# ext_supply_con.net
KiCad netlist of a schematic drawn in Altium Designer
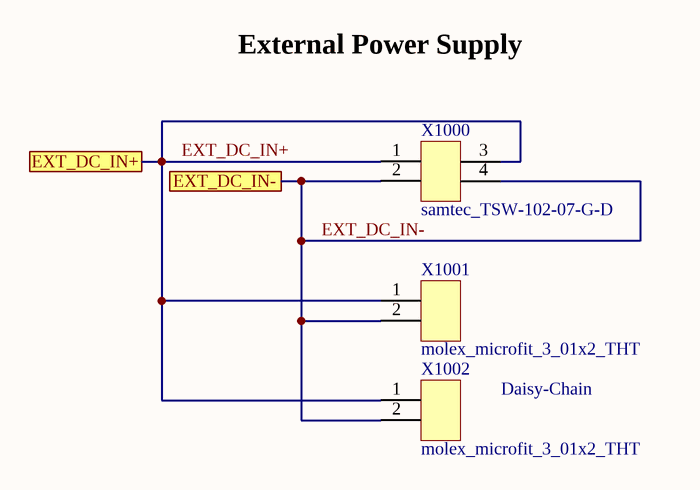
[diagram p0: ext_supply_con.SchDoc]

(export (version "E")
  (design (tool "Eeschema 10.0.6"))
  (components
    (comp (ref "X1000")
      (value "samtec_TSW-102-07-G-D")
      (footprint "Pinheader_2.54_2x2")
      (description "Board-To-Board Connector, Vertical, 2.54 mm, 4 Contacts, Header, TSW Series, Through Hole, 2 Rows")
      (fields (field (name "MANUFACTURER") "Samtec"))
      (libsource (lib "OE750") (part "X2x2"))
    )
    (comp (ref "X1001")
      (value "molex_microfit_3_01x2_THT")
      (footprint "MOLEX_MICROFIT_01x2_THT")
      (fields (field (name "MANUFACTURER") "Molex"))
      (libsource (lib "OE750") (part "X2"))
    )
    (comp (ref "X1002")
      (value "molex_microfit_3_01x2_THT")
      (footprint "MOLEX_MICROFIT_01x2_THT")
      (fields (field (name "MANUFACTURER") "Molex"))
      (libsource (lib "OE750") (part "X2"))
    )
  )
  (nets
    (net (code "1") (name "/EXT_DC_IN+") (class "Default")
      (node (ref "X1000") (pin "1") (pintype "passive"))
      (node (ref "X1000") (pin "3") (pintype "passive"))
      (node (ref "X1001") (pin "1") (pintype "passive"))
      (node (ref "X1002") (pin "1") (pintype "passive"))
    )
    (net (code "2") (name "/EXT_DC_IN-") (class "Default")
      (node (ref "X1000") (pin "2") (pintype "passive"))
      (node (ref "X1000") (pin "4") (pintype "passive"))
      (node (ref "X1001") (pin "2") (pintype "passive"))
      (node (ref "X1002") (pin "2") (pintype "passive"))
    )
  )
)
